# Ports_and_Display.net
KiCad netlist of a schematic drawn in Altium Designer
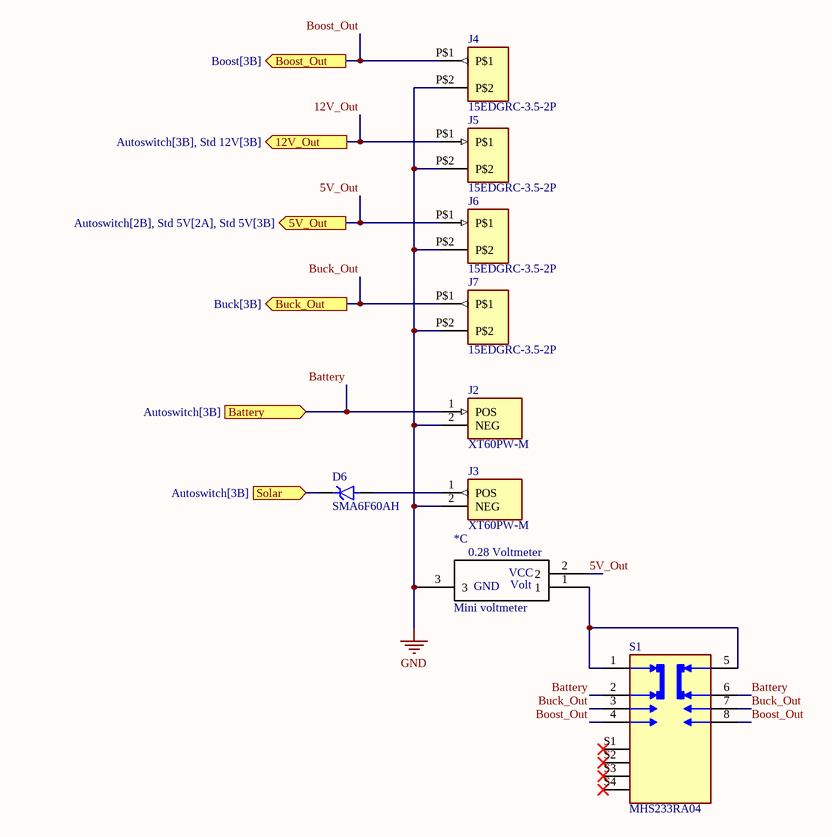
[diagram p0: Ports and Display.SchDoc]

(export (version "E")
  (design (tool "Eeschema 10.0.6"))
  (components
    (comp (ref "*")
      (value "Mini voltmeter")
      (footprint "New footprint 1")
      (description "0-100V")
      (libsource (lib "Vedant Ashtankar") (part "New symbol 1"))
    )
    (comp (ref "D6")
      (value "SMA6F60AH")
      (footprint "SODFL5226X100N")
      (description "600W, 70.6V, 5%, Unidirectional, TVS")
      (fields (field (name "MF") "Taiwan Semiconductor"))
      (libsource (lib "Vedant Ashtankar") (part "SMA6F60AH"))
    )
    (comp (ref "J2")
      (value "XT60PW-M")
      (footprint "AMASS_XT60PW-M")
      (description "Socket, DC supply, male, PIN: 2")
      (fields (field (name "MF") "AMASS"))
      (libsource (lib "Vedant Ashtankar") (part "XT60PW-M"))
    )
    (comp (ref "J3")
      (value "XT60PW-M")
      (footprint "AMASS_XT60PW-M")
      (description "Socket, DC supply, male, PIN: 2")
      (fields (field (name "MF") "AMASS"))
      (libsource (lib "Vedant Ashtankar") (part "XT60PW-M"))
    )
    (comp (ref "J4")
      (value "15EDGRC-3.5-2P")
      (footprint "15EDGRC-3.5-2P-PAK")
      (description "Pluggable terminal block; socket; male; 3.5mm; angled 90Â°; ways: 2")
      (fields (field (name "MF") "Degson") (field (name "MP") "15EDGRC-3.5/2P"))
      (libsource (lib "Vedant Ashtankar") (part "15EDGRC-3.5-2P"))
    )
    (comp (ref "J5")
      (value "15EDGRC-3.5-2P")
      (footprint "15EDGRC-3.5-2P-PAK")
      (description "Pluggable terminal block; socket; male; 3.5mm; angled 90Â°; ways: 2")
      (fields (field (name "MF") "Degson") (field (name "MP") "15EDGRC-3.5/2P"))
      (libsource (lib "Vedant Ashtankar") (part "15EDGRC-3.5-2P"))
    )
    (comp (ref "J6")
      (value "15EDGRC-3.5-2P")
      (footprint "15EDGRC-3.5-2P-PAK")
      (description "Pluggable terminal block; socket; male; 3.5mm; angled 90Â°; ways: 2")
      (fields (field (name "MF") "Degson") (field (name "MP") "15EDGRC-3.5/2P"))
      (libsource (lib "Vedant Ashtankar") (part "15EDGRC-3.5-2P"))
    )
    (comp (ref "J7")
      (value "15EDGRC-3.5-2P")
      (footprint "15EDGRC-3.5-2P-PAK")
      (description "Pluggable terminal block; socket; male; 3.5mm; angled 90Â°; ways: 2")
      (fields (field (name "MF") "Degson") (field (name "MP") "15EDGRC-3.5/2P"))
      (libsource (lib "Vedant Ashtankar") (part "15EDGRC-3.5-2P"))
    )
    (comp (ref "S1")
      (value "MHS233RA04")
      (footprint "SW_MHS233RA04")
      (description "Switch Slide ON ON ON DP3T Side Slide 0.3A 125VAC PC Pins Bracket Mount/Through Hole Tray")
      (fields (field (name "MF") "TE Connectivity"))
      (libsource (lib "Vedant Ashtankar") (part "MHS233RA04"))
    )
  )
  (nets
    (net (code "1") (name "/5V_Out") (class "Default")
      (node (ref "*") (pin "2") (pinfunction "2_2") (pintype "passive"))
      (node (ref "J6") (pin "P$1") (pinfunction "P$1_P$1") (pintype "output"))
    )
    (net (code "2") (name "/12V_Out") (class "Default")
      (node (ref "J5") (pin "P$1") (pinfunction "P$1_P$1") (pintype "output"))
    )
    (net (code "3") (name "/Battery") (class "Default")
      (node (ref "J2") (pin "1") (pinfunction "POS_1") (pintype "input"))
      (node (ref "S1") (pin "2") (pinfunction "2_2") (pintype "passive"))
      (node (ref "S1") (pin "6") (pinfunction "6_6") (pintype "passive"))
    )
    (net (code "4") (name "/Boost_Out") (class "Default")
      (node (ref "J4") (pin "P$1") (pinfunction "P$1_P$1") (pintype "output"))
      (node (ref "S1") (pin "4") (pinfunction "4_4") (pintype "passive"))
      (node (ref "S1") (pin "8") (pinfunction "8_8") (pintype "passive"))
    )
    (net (code "5") (name "/Buck_Out") (class "Default")
      (node (ref "J7") (pin "P$1") (pinfunction "P$1_P$1") (pintype "output"))
      (node (ref "S1") (pin "3") (pinfunction "3_3") (pintype "passive"))
      (node (ref "S1") (pin "7") (pinfunction "7_7") (pintype "passive"))
    )
    (net (code "6") (name "/Solar") (class "Default")
      (node (ref "D6") (pin "1") (pinfunction "K_1") (pintype "passive"))
    )
    (net (code "7") (name "GND") (class "Default")
      (node (ref "*") (pin "3") (pinfunction "3_3") (pintype "passive"))
      (node (ref "J2") (pin "2") (pinfunction "NEG_2") (pintype "power_in"))
      (node (ref "J3") (pin "2") (pinfunction "NEG_2") (pintype "power_in"))
      (node (ref "J4") (pin "P$2") (pinfunction "P$2_P$2") (pintype "power_in"))
      (node (ref "J5") (pin "P$2") (pinfunction "P$2_P$2") (pintype "power_in"))
      (node (ref "J6") (pin "P$2") (pinfunction "P$2_P$2") (pintype "power_in"))
      (node (ref "J7") (pin "P$2") (pinfunction "P$2_P$2") (pintype "power_in"))
    )
    (net (code "8") (name "Net-(*-Pad1)") (class "Default")
      (node (ref "*") (pin "1") (pinfunction "1_1") (pintype "passive"))
      (node (ref "S1") (pin "1") (pinfunction "1_1") (pintype "passive"))
      (node (ref "S1") (pin "5") (pinfunction "5_5") (pintype "passive"))
    )
    (net (code "9") (name "Net-(D6-A)") (class "Default")
      (node (ref "D6") (pin "2") (pinfunction "A_2") (pintype "passive"))
      (node (ref "J3") (pin "1") (pinfunction "POS_1") (pintype "input"))
    )
    (net (code "10") (name "unconnected-(S1-SHIELD-PadS1)") (class "Default")
      (node (ref "S1") (pin "S1") (pinfunction "SHIELD_S1") (pintype "passive+no_connect"))
    )
    (net (code "11") (name "unconnected-(S1-SHIELD-PadS2)") (class "Default")
      (node (ref "S1") (pin "S2") (pinfunction "SHIELD_S2") (pintype "passive+no_connect"))
    )
    (net (code "12") (name "unconnected-(S1-SHIELD-PadS3)") (class "Default")
      (node (ref "S1") (pin "S3") (pinfunction "SHIELD_S3") (pintype "passive+no_connect"))
    )
    (net (code "13") (name "unconnected-(S1-SHIELD-PadS4)") (class "Default")
      (node (ref "S1") (pin "S4") (pinfunction "SHIELD_S4") (pintype "passive+no_connect"))
    )
  )
)
